# SpiritLevel.net
KiCad netlist of a schematic drawn in EAGLE
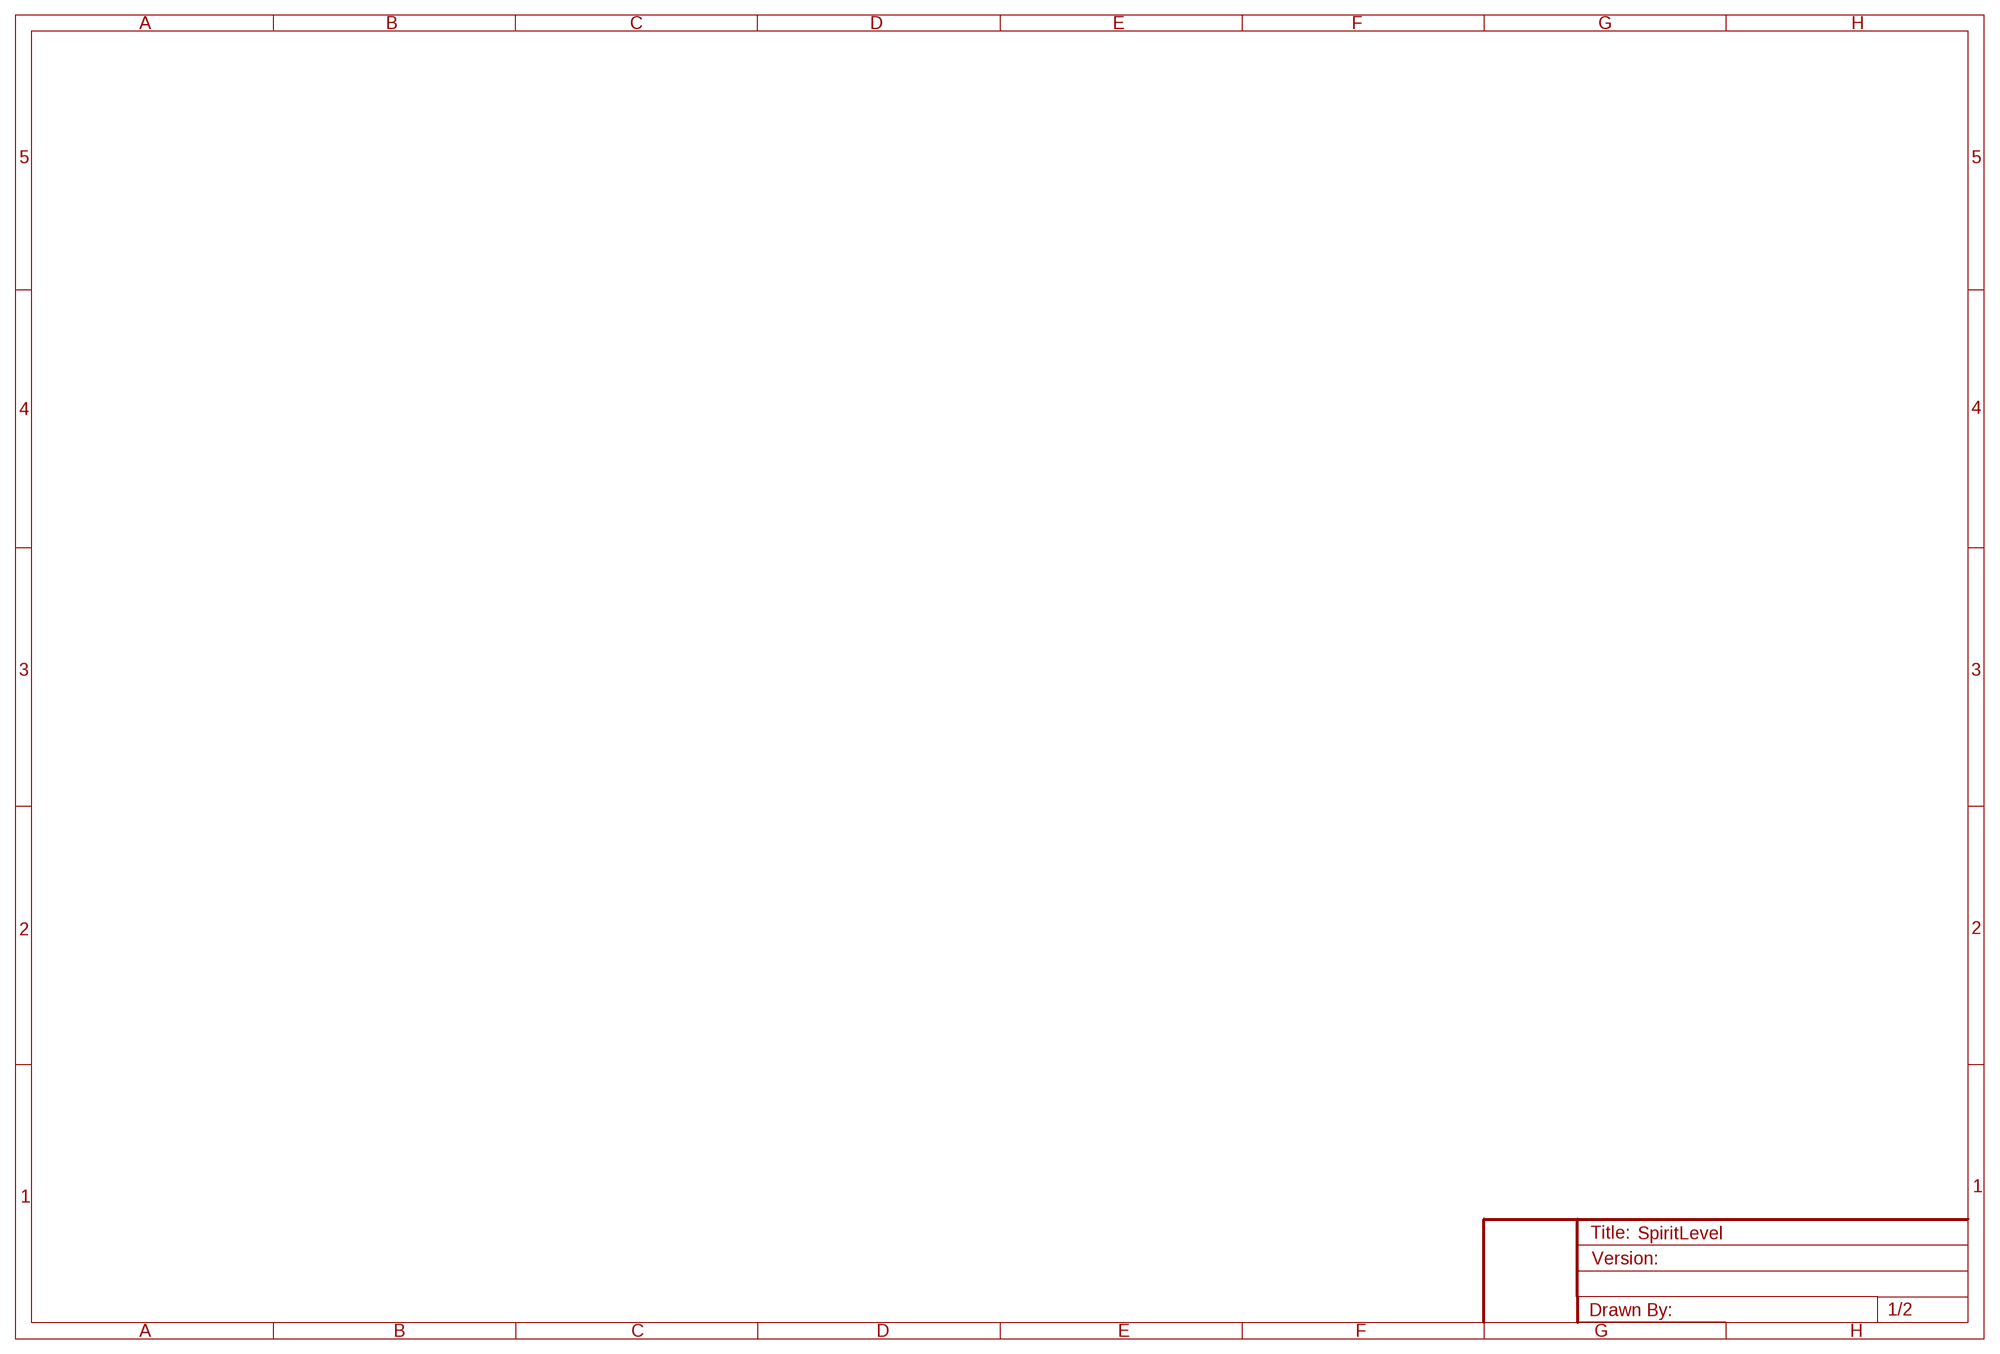
[diagram p0: schematic, sheet 1]
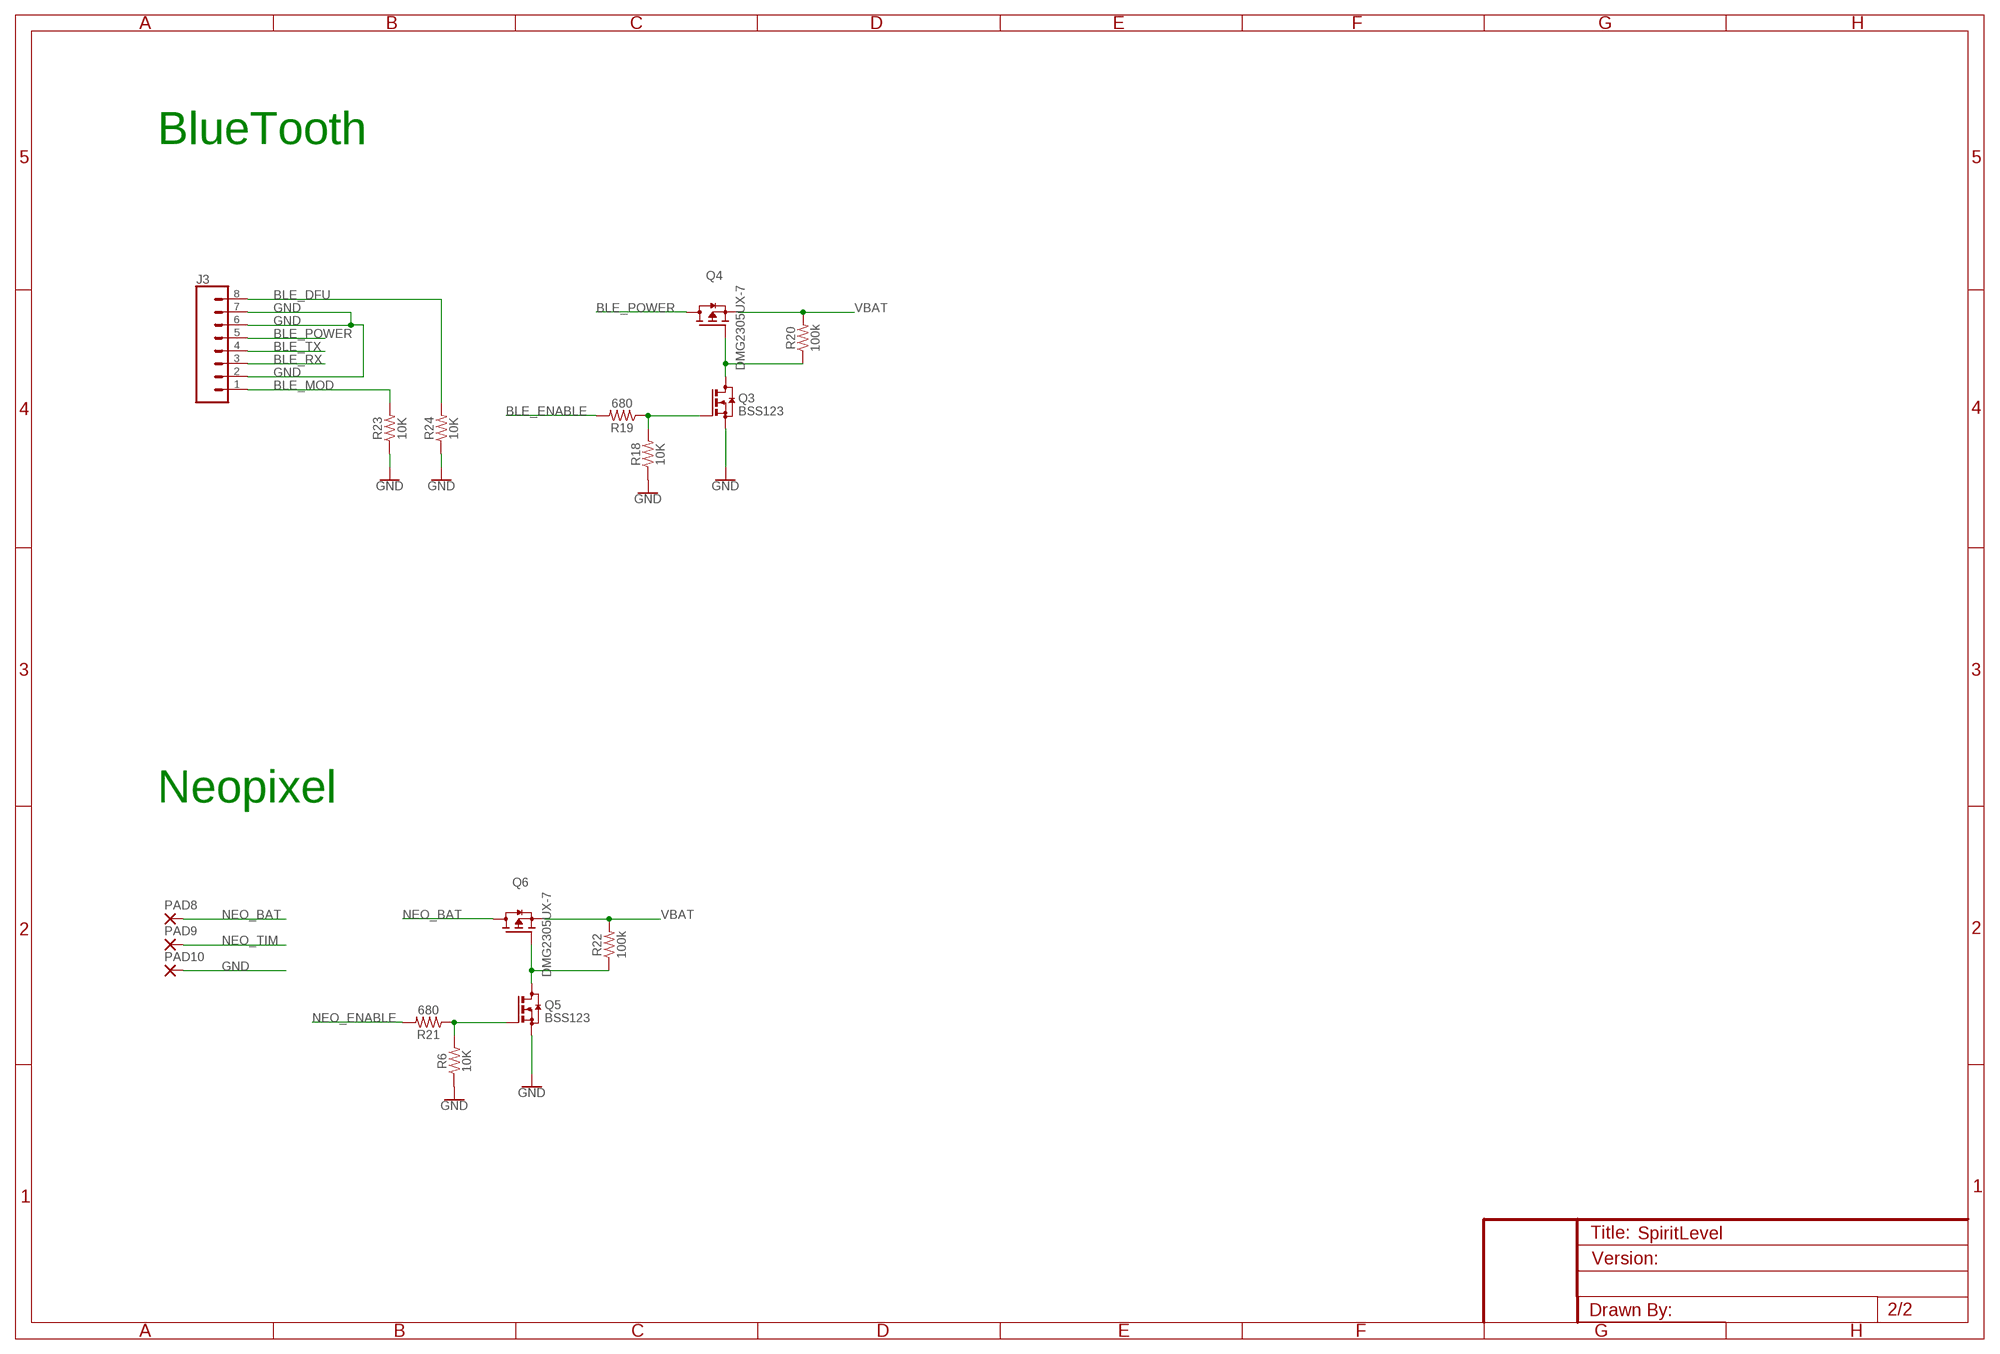
[diagram p1: schematic, sheet 2]

(export (version "E")
  (design (tool "Eeschema 10.0.6"))
  (components
    (comp (ref "J3")
      (value "CONN_08FEMALE_LOCK")
      (footprint "eagle-import:1X08_FEMALE_LOCK")
      (libsource (lib "eagle-import") (part "CONN_08FEMALE_LOCK"))
    )
    (comp (ref "PAD8")
      (value "SMD5")
      (footprint "eagle-import:SMD2,54-5,08")
      (libsource (lib "eagle-import") (part "SMD5"))
    )
    (comp (ref "PAD9")
      (value "SMD5")
      (footprint "eagle-import:SMD2,54-5,08")
      (libsource (lib "eagle-import") (part "SMD5"))
    )
    (comp (ref "PAD10")
      (value "SMD5")
      (footprint "eagle-import:SMD2,54-5,08")
      (libsource (lib "eagle-import") (part "SMD5"))
    )
    (comp (ref "Q3")
      (value "BSS123")
      (footprint "eagle-import:SOT23")
      (libsource (lib "eagle-import") (part "BSS123"))
    )
    (comp (ref "Q4")
      (value "DMG2305UX-7")
      (footprint "eagle-import:SOT91P240X110-3N_DMG2305UX-7")
      (fields (field (name "MF") "Diodes Inc."))
      (libsource (lib "eagle-import") (part "DMG2305UX-7"))
    )
    (comp (ref "Q5")
      (value "BSS123")
      (footprint "eagle-import:SOT23")
      (libsource (lib "eagle-import") (part "BSS123"))
    )
    (comp (ref "Q6")
      (value "DMG2305UX-7")
      (footprint "eagle-import:SOT91P240X110-3N_DMG2305UX-7")
      (fields (field (name "MF") "Diodes Inc."))
      (libsource (lib "eagle-import") (part "DMG2305UX-7"))
    )
    (comp (ref "R6")
      (value "10K")
      (footprint "eagle-import:0402")
      (libsource (lib "eagle-import") (part "100KOHM-0402-1/16W-1%"))
    )
    (comp (ref "R18")
      (value "10K")
      (footprint "eagle-import:0402")
      (libsource (lib "eagle-import") (part "100KOHM-0402-1/16W-1%"))
    )
    (comp (ref "R19")
      (value "680")
      (footprint "eagle-import:0402")
      (libsource (lib "eagle-import") (part "100KOHM-0402-1/16W-1%"))
    )
    (comp (ref "R20")
      (value "100k")
      (footprint "eagle-import:0603")
      (libsource (lib "eagle-import") (part "100KOHM-0603-1/10W-1%"))
    )
    (comp (ref "R21")
      (value "680")
      (footprint "eagle-import:0402")
      (libsource (lib "eagle-import") (part "100KOHM-0402-1/16W-1%"))
    )
    (comp (ref "R22")
      (value "100k")
      (footprint "eagle-import:0603")
      (libsource (lib "eagle-import") (part "100KOHM-0603-1/10W-1%"))
    )
    (comp (ref "R23")
      (value "10K")
      (footprint "eagle-import:0402")
      (libsource (lib "eagle-import") (part "100KOHM-0402-1/16W-1%"))
    )
    (comp (ref "R24")
      (value "10K")
      (footprint "eagle-import:0402")
      (libsource (lib "eagle-import") (part "100KOHM-0402-1/16W-1%"))
    )
  )
  (nets
    (net (code "1") (name "BLE_DFU") (class "Default")
      (node (ref "J3") (pin "8") (pinfunction "8_8") (pintype "passive"))
      (node (ref "R24") (pin "2") (pinfunction "2_2") (pintype "passive"))
    )
    (net (code "2") (name "BLE_ENABLE") (class "Default")
      (node (ref "R19") (pin "2") (pinfunction "2_2") (pintype "passive"))
    )
    (net (code "3") (name "BLE_MOD") (class "Default")
      (node (ref "J3") (pin "1") (pinfunction "1_1") (pintype "passive"))
      (node (ref "R23") (pin "2") (pinfunction "2_2") (pintype "passive"))
    )
    (net (code "4") (name "BLE_POWER") (class "Default")
      (node (ref "J3") (pin "5") (pinfunction "5_5") (pintype "passive"))
      (node (ref "Q4") (pin "3") (pinfunction "D_3") (pintype "passive"))
    )
    (net (code "5") (name "BLE_RX") (class "Default")
      (node (ref "J3") (pin "3") (pinfunction "3_3") (pintype "passive"))
    )
    (net (code "6") (name "BLE_TX") (class "Default")
      (node (ref "J3") (pin "4") (pinfunction "4_4") (pintype "passive"))
    )
    (net (code "7") (name "GND") (class "Default")
      (node (ref "J3") (pin "2") (pinfunction "2_2") (pintype "passive"))
      (node (ref "J3") (pin "6") (pinfunction "6_6") (pintype "passive"))
      (node (ref "J3") (pin "7") (pinfunction "7_7") (pintype "passive"))
      (node (ref "PAD10") (pin "1") (pinfunction "P_1") (pintype "passive"))
      (node (ref "Q3") (pin "2") (pinfunction "S_2") (pintype "passive"))
      (node (ref "Q5") (pin "2") (pinfunction "S_2") (pintype "passive"))
      (node (ref "R18") (pin "1") (pinfunction "1_1") (pintype "passive"))
      (node (ref "R23") (pin "1") (pinfunction "1_1") (pintype "passive"))
      (node (ref "R24") (pin "1") (pinfunction "1_1") (pintype "passive"))
      (node (ref "R6") (pin "1") (pinfunction "1_1") (pintype "passive"))
    )
    (net (code "8") (name "NEO_BAT") (class "Default")
      (node (ref "PAD8") (pin "1") (pinfunction "P_1") (pintype "passive"))
      (node (ref "Q6") (pin "3") (pinfunction "D_3") (pintype "passive"))
    )
    (net (code "9") (name "NEO_ENABLE") (class "Default")
      (node (ref "R21") (pin "2") (pinfunction "2_2") (pintype "passive"))
    )
    (net (code "10") (name "NEO_TIM") (class "Default")
      (node (ref "PAD9") (pin "1") (pinfunction "P_1") (pintype "passive"))
    )
    (net (code "11") (name "Net-(Q3-D)") (class "Default")
      (node (ref "Q3") (pin "3") (pinfunction "D_3") (pintype "passive"))
      (node (ref "Q4") (pin "1") (pinfunction "G_1") (pintype "passive"))
      (node (ref "R20") (pin "1") (pinfunction "1_1") (pintype "passive"))
    )
    (net (code "12") (name "Net-(Q3-G)") (class "Default")
      (node (ref "Q3") (pin "1") (pinfunction "G_1") (pintype "passive"))
      (node (ref "R18") (pin "2") (pinfunction "2_2") (pintype "passive"))
      (node (ref "R19") (pin "1") (pinfunction "1_1") (pintype "passive"))
    )
    (net (code "13") (name "Net-(Q5-D)") (class "Default")
      (node (ref "Q5") (pin "3") (pinfunction "D_3") (pintype "passive"))
      (node (ref "Q6") (pin "1") (pinfunction "G_1") (pintype "passive"))
      (node (ref "R22") (pin "1") (pinfunction "1_1") (pintype "passive"))
    )
    (net (code "14") (name "Net-(Q5-G)") (class "Default")
      (node (ref "Q5") (pin "1") (pinfunction "G_1") (pintype "passive"))
      (node (ref "R21") (pin "1") (pinfunction "1_1") (pintype "passive"))
      (node (ref "R6") (pin "2") (pinfunction "2_2") (pintype "passive"))
    )
    (net (code "15") (name "VBAT") (class "Default")
      (node (ref "Q4") (pin "2") (pinfunction "S_2") (pintype "passive"))
      (node (ref "Q6") (pin "2") (pinfunction "S_2") (pintype "passive"))
      (node (ref "R20") (pin "2") (pinfunction "2_2") (pintype "passive"))
      (node (ref "R22") (pin "2") (pinfunction "2_2") (pintype "passive"))
    )
  )
)
